# NEG_2_5_BOB.net
KiCad netlist of a schematic drawn in EAGLE
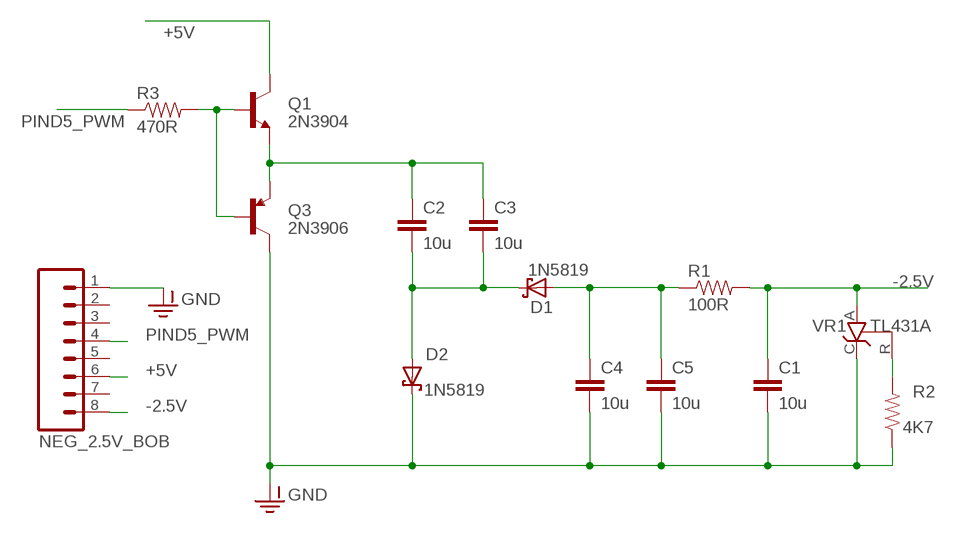
[diagram p0: schematic, sheet 1]

(export (version "E")
  (design (tool "Eeschema 10.0.6"))
  (components
    (comp (ref "C1")
      (value "10u")
      (footprint "eagle-import:CAP-PTH-5MM")
      (libsource (lib "eagle-import") (part "CAPPTH1"))
    )
    (comp (ref "C2")
      (value "10u")
      (footprint "eagle-import:CAP-PTH-5MM")
      (libsource (lib "eagle-import") (part "CAPPTH1"))
    )
    (comp (ref "C3")
      (value "10u")
      (footprint "eagle-import:CAP-PTH-5MM")
      (libsource (lib "eagle-import") (part "CAPPTH1"))
    )
    (comp (ref "C4")
      (value "10u")
      (footprint "eagle-import:CAP-PTH-5MM")
      (libsource (lib "eagle-import") (part "CAPPTH1"))
    )
    (comp (ref "C5")
      (value "10u")
      (footprint "eagle-import:CAP-PTH-5MM")
      (libsource (lib "eagle-import") (part "CAPPTH1"))
    )
    (comp (ref "D1")
      (value "1N5819")
      (footprint "eagle-import:DO41-7.6")
      (libsource (lib "eagle-import") (part "1N5819-B"))
    )
    (comp (ref "D2")
      (value "1N5819")
      (footprint "eagle-import:DO41-7.6")
      (libsource (lib "eagle-import") (part "1N5819-B"))
    )
    (comp (ref "NEG_2.5V_BOB")
      (value "M08")
      (footprint "eagle-import:1X08_ROUND")
      (libsource (lib "eagle-import") (part "M08"))
    )
    (comp (ref "Q1")
      (value "2N3904")
      (footprint "eagle-import:TO-92")
      (libsource (lib "eagle-import") (part "TRANSISTOR_NPN2N3904"))
    )
    (comp (ref "Q3")
      (value "2N3906")
      (footprint "eagle-import:TO-92")
      (libsource (lib "eagle-import") (part "TRANSISTOR_PNPTO92"))
    )
    (comp (ref "R1")
      (value "100R")
      (footprint "eagle-import:AXIAL-0.4")
      (libsource (lib "eagle-import") (part "RESISTORPTH-1/4W"))
    )
    (comp (ref "R2")
      (value "4K7")
      (footprint "eagle-import:AXIAL-0.4")
      (libsource (lib "eagle-import") (part "RESISTORPTH-1/4W"))
    )
    (comp (ref "R3")
      (value "470R")
      (footprint "eagle-import:AXIAL-0.4")
      (libsource (lib "eagle-import") (part "RESISTORPTH-1/4W"))
    )
    (comp (ref "VR1")
      (value "TL431A")
      (footprint "eagle-import:TO92-CLP")
      (libsource (lib "eagle-import") (part "TL431CLP"))
    )
  )
  (nets
    (net (code "1") (name "/+5V") (class "Default")
      (node (ref "NEG_2.5V_BOB") (pin "6") (pinfunction "6_6") (pintype "passive"))
      (node (ref "Q1") (pin "3") (pinfunction "C_3") (pintype "passive"))
    )
    (net (code "2") (name "/-2.5V") (class "Default")
      (node (ref "C1") (pin "1") (pinfunction "1_1") (pintype "passive"))
      (node (ref "NEG_2.5V_BOB") (pin "8") (pinfunction "8_8") (pintype "passive"))
      (node (ref "R1") (pin "P$2") (pinfunction "2_P$2") (pintype "passive"))
      (node (ref "VR1") (pin "A") (pinfunction "A_A") (pintype "passive"))
    )
    (net (code "3") (name "/PIND5_PWM") (class "Default")
      (node (ref "NEG_2.5V_BOB") (pin "4") (pinfunction "4_4") (pintype "passive"))
      (node (ref "R3") (pin "P$1") (pinfunction "1_P$1") (pintype "passive"))
    )
    (net (code "4") (name "GND") (class "Default")
      (node (ref "C1") (pin "2") (pinfunction "2_2") (pintype "passive"))
      (node (ref "C4") (pin "2") (pinfunction "2_2") (pintype "passive"))
      (node (ref "C5") (pin "2") (pinfunction "2_2") (pintype "passive"))
      (node (ref "D2") (pin "C") (pinfunction "C_C") (pintype "passive"))
      (node (ref "NEG_2.5V_BOB") (pin "1") (pinfunction "1_1") (pintype "passive"))
      (node (ref "Q3") (pin "3") (pinfunction "C_3") (pintype "passive"))
      (node (ref "R2") (pin "P$1") (pinfunction "1_P$1") (pintype "passive"))
      (node (ref "VR1") (pin "C") (pinfunction "C_C") (pintype "passive"))
    )
    (net (code "5") (name "Net-(C2-Pad2)") (class "Default")
      (node (ref "C2") (pin "2") (pinfunction "2_2") (pintype "passive"))
      (node (ref "C3") (pin "2") (pinfunction "2_2") (pintype "passive"))
      (node (ref "D1") (pin "C") (pinfunction "C_C") (pintype "passive"))
      (node (ref "D2") (pin "A") (pinfunction "A_A") (pintype "passive"))
    )
    (net (code "6") (name "Net-(Q1-B)") (class "Default")
      (node (ref "Q1") (pin "2") (pinfunction "B_2") (pintype "passive"))
      (node (ref "Q3") (pin "2") (pinfunction "B_2") (pintype "passive"))
      (node (ref "R3") (pin "P$2") (pinfunction "2_P$2") (pintype "passive"))
    )
    (net (code "7") (name "Net-(Q1-E)") (class "Default")
      (node (ref "C2") (pin "1") (pinfunction "1_1") (pintype "passive"))
      (node (ref "C3") (pin "1") (pinfunction "1_1") (pintype "passive"))
      (node (ref "Q1") (pin "1") (pinfunction "E_1") (pintype "passive"))
      (node (ref "Q3") (pin "1") (pinfunction "E_1") (pintype "passive"))
    )
    (net (code "8") (name "Net-(R1-1)") (class "Default")
      (node (ref "C4") (pin "1") (pinfunction "1_1") (pintype "passive"))
      (node (ref "C5") (pin "1") (pinfunction "1_1") (pintype "passive"))
      (node (ref "D1") (pin "A") (pinfunction "A_A") (pintype "passive"))
      (node (ref "R1") (pin "P$1") (pinfunction "1_P$1") (pintype "passive"))
    )
    (net (code "9") (name "Net-(R2-2)") (class "Default")
      (node (ref "R2") (pin "P$2") (pinfunction "2_P$2") (pintype "passive"))
      (node (ref "VR1") (pin "R") (pinfunction "R_R") (pintype "passive"))
    )
    (net (code "10") (name "unconnected-(NEG_2.5V_BOB-Pad2)") (class "Default")
      (node (ref "NEG_2.5V_BOB") (pin "2") (pinfunction "2_2") (pintype "passive"))
    )
    (net (code "11") (name "unconnected-(NEG_2.5V_BOB-Pad3)") (class "Default")
      (node (ref "NEG_2.5V_BOB") (pin "3") (pinfunction "3_3") (pintype "passive"))
    )
    (net (code "12") (name "unconnected-(NEG_2.5V_BOB-Pad5)") (class "Default")
      (node (ref "NEG_2.5V_BOB") (pin "5") (pinfunction "5_5") (pintype "passive"))
    )
    (net (code "13") (name "unconnected-(NEG_2.5V_BOB-Pad7)") (class "Default")
      (node (ref "NEG_2.5V_BOB") (pin "7") (pinfunction "7_7") (pintype "passive"))
    )
  )
)
